# queso_dip_v5.net
KiCad netlist of a schematic drawn in EAGLE
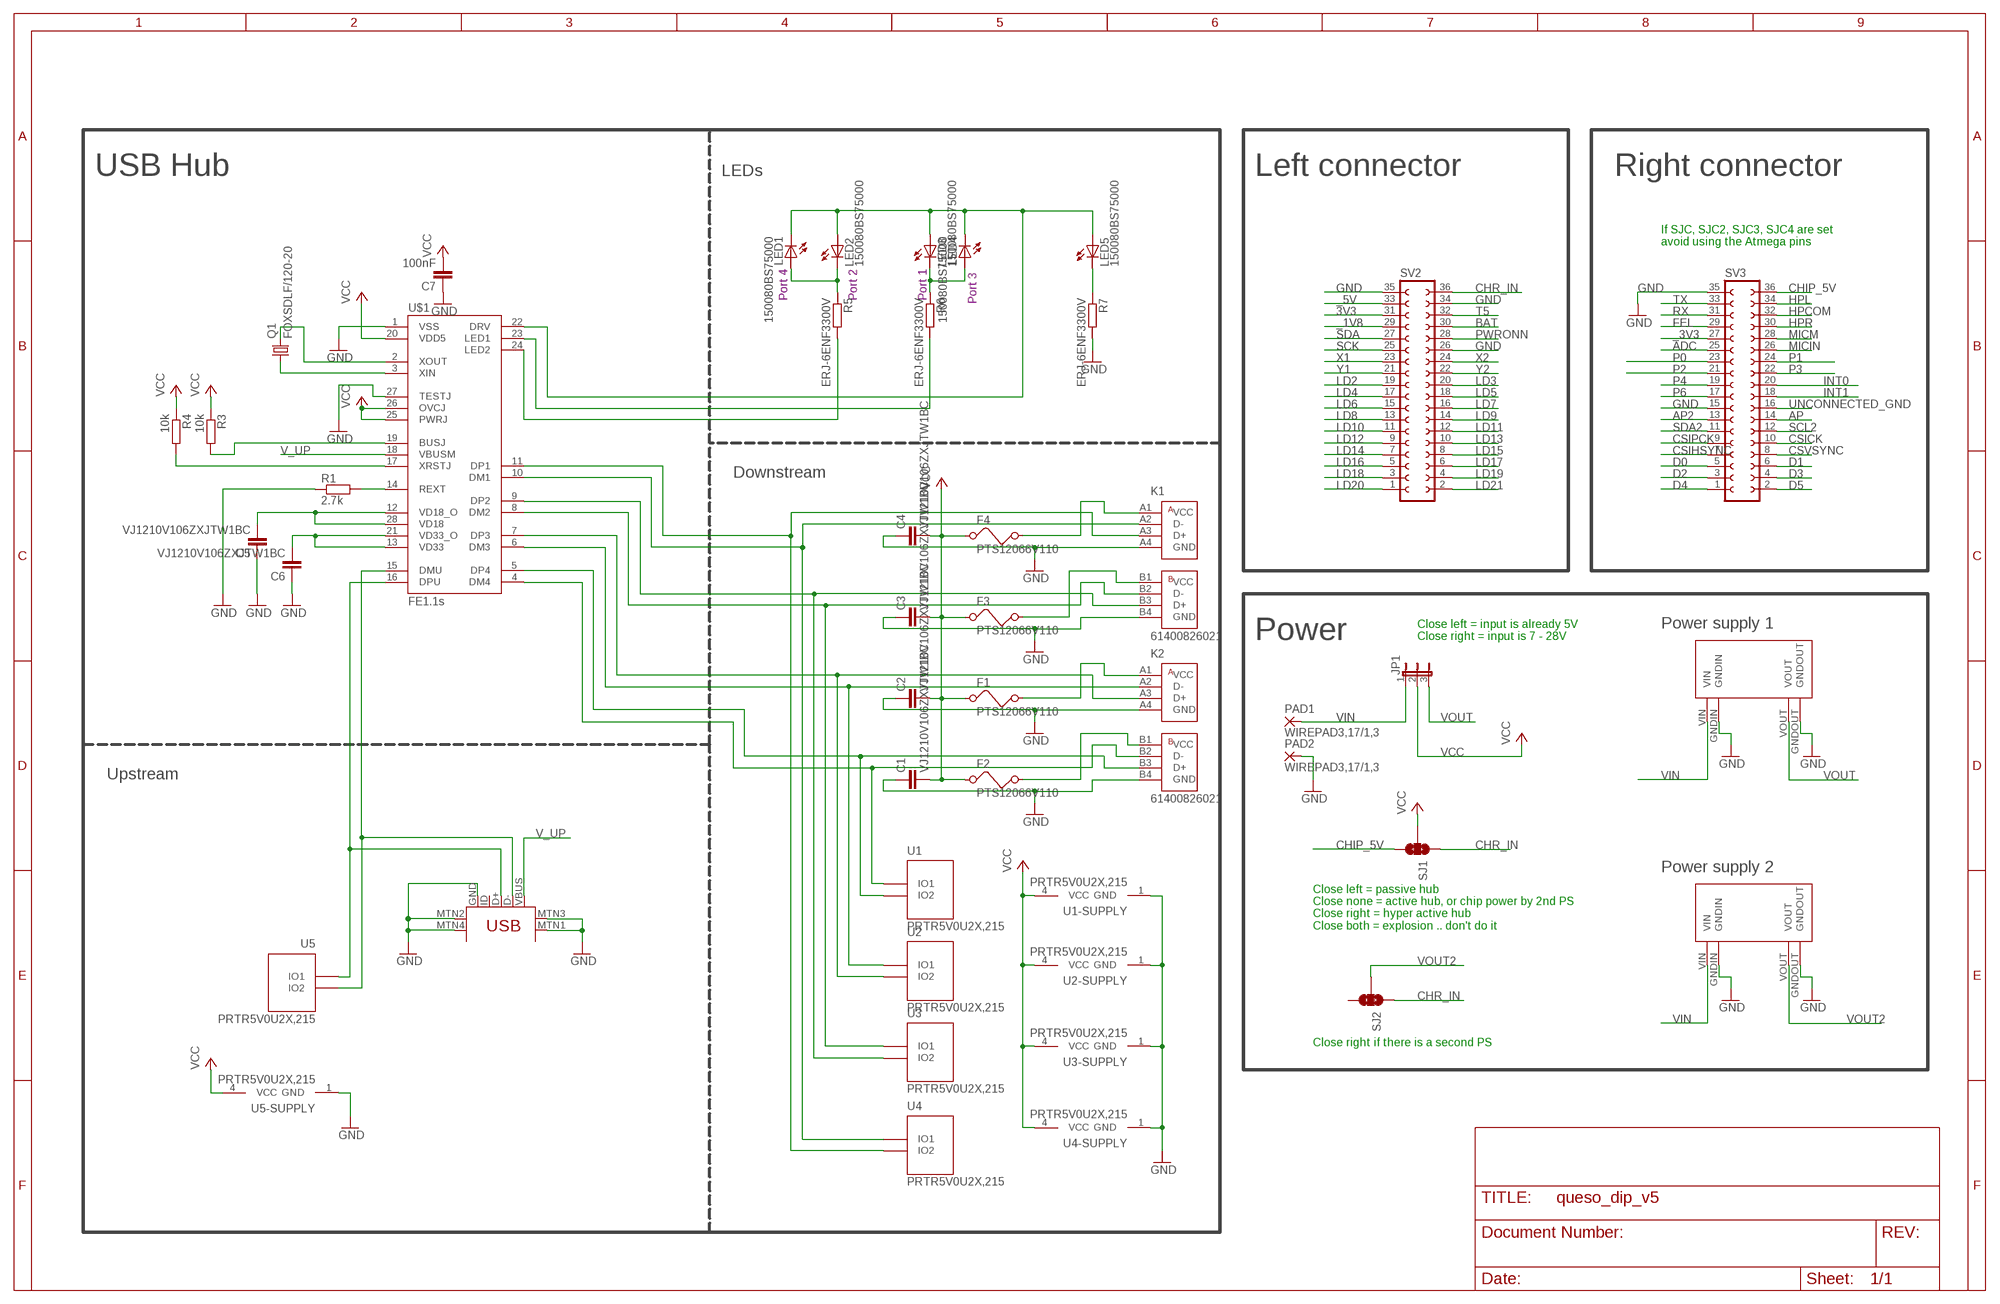
[diagram p0: schematic, sheet 1]

(export (version "E")
  (design (tool "Eeschema 10.0.6"))
  (components
    (comp (ref "C1")
      (value "VJ1210V106ZXJTW1BC")
      (footprint "eagle-import:C1210")
      (libsource (lib "eagle-import") (part "C-EUC1210"))
    )
    (comp (ref "C2")
      (value "VJ1210V106ZXJTW1BC")
      (footprint "eagle-import:C1210")
      (libsource (lib "eagle-import") (part "C-EUC1210"))
    )
    (comp (ref "C3")
      (value "VJ1210V106ZXJTW1BC")
      (footprint "eagle-import:C1210")
      (libsource (lib "eagle-import") (part "C-EUC1210"))
    )
    (comp (ref "C4")
      (value "VJ1210V106ZXJTW1BC")
      (footprint "eagle-import:C1210")
      (libsource (lib "eagle-import") (part "C-EUC1210"))
    )
    (comp (ref "C5")
      (value "VJ1210V106ZXJTW1BC")
      (footprint "eagle-import:C1210")
      (libsource (lib "eagle-import") (part "C-EUC1210"))
    )
    (comp (ref "C6")
      (value "VJ1210V106ZXJTW1BC")
      (footprint "eagle-import:C1210")
      (libsource (lib "eagle-import") (part "C-EUC1210"))
    )
    (comp (ref "C7")
      (value "100nF")
      (footprint "eagle-import:C0805")
      (libsource (lib "eagle-import") (part "C-EUC0805"))
    )
    (comp (ref "F1")
      (value "PTS12066V110")
      (footprint "eagle-import:1210")
      (libsource (lib "eagle-import") (part "FUSED"))
    )
    (comp (ref "F2")
      (value "PTS12066V110")
      (footprint "eagle-import:1210")
      (libsource (lib "eagle-import") (part "FUSED"))
    )
    (comp (ref "F3")
      (value "PTS12066V110")
      (footprint "eagle-import:1210")
      (libsource (lib "eagle-import") (part "FUSED"))
    )
    (comp (ref "F4")
      (value "PTS12066V110")
      (footprint "eagle-import:1210")
      (libsource (lib "eagle-import") (part "FUSED"))
    )
    (comp (ref "JP1")
      (value "JP2E")
      (footprint "eagle-import:JP2")
      (libsource (lib "eagle-import") (part "JP2E"))
    )
    (comp (ref "K1")
      (value "61400826021")
      (footprint "eagle-import:61400826021")
      (libsource (lib "eagle-import") (part "61400826021"))
    )
    (comp (ref "K2")
      (value "61400826021")
      (footprint "eagle-import:61400826021")
      (libsource (lib "eagle-import") (part "61400826021"))
    )
    (comp (ref "LED1")
      (value "150080BS75000")
      (footprint "eagle-import:CHIP-LED0805")
      (libsource (lib "eagle-import") (part "LEDCHIP-LED0805"))
    )
    (comp (ref "LED2")
      (value "150080BS75000")
      (footprint "eagle-import:CHIP-LED0805")
      (libsource (lib "eagle-import") (part "LEDCHIP-LED0805"))
    )
    (comp (ref "LED3")
      (value "150080BS75000")
      (footprint "eagle-import:CHIP-LED0805")
      (libsource (lib "eagle-import") (part "LEDCHIP-LED0805"))
    )
    (comp (ref "LED4")
      (value "150080BS75000")
      (footprint "eagle-import:CHIP-LED0805")
      (libsource (lib "eagle-import") (part "LEDCHIP-LED0805"))
    )
    (comp (ref "LED5")
      (value "150080BS75000")
      (footprint "eagle-import:CHIP-LED0805")
      (libsource (lib "eagle-import") (part "LEDCHIP-LED0805"))
    )
    (comp (ref "PAD1")
      (value "WIREPAD3,17/1,3")
      (footprint "eagle-import:3,17_1,3")
      (libsource (lib "eagle-import") (part "WIREPAD3,17/1,3"))
    )
    (comp (ref "PAD2")
      (value "WIREPAD3,17/1,3")
      (footprint "eagle-import:3,17_1,3")
      (libsource (lib "eagle-import") (part "WIREPAD3,17/1,3"))
    )
    (comp (ref "Q1")
      (value "FOXSDLF/120-20")
      (footprint "eagle-import:SM49")
      (libsource (lib "eagle-import") (part "CRYSTALSM49"))
    )
    (comp (ref "R1")
      (value "2.7k")
      (footprint "eagle-import:R0805")
      (libsource (lib "eagle-import") (part "R-EU_R0805"))
    )
    (comp (ref "R3")
      (value "10k")
      (footprint "eagle-import:R0805")
      (libsource (lib "eagle-import") (part "R-EU_R0805"))
    )
    (comp (ref "R4")
      (value "10k")
      (footprint "eagle-import:R0805")
      (libsource (lib "eagle-import") (part "R-EU_R0805"))
    )
    (comp (ref "R5")
      (value "ERJ-6ENF3300V")
      (footprint "eagle-import:R0805")
      (libsource (lib "eagle-import") (part "R-EU_R0805"))
    )
    (comp (ref "R6")
      (value "ERJ-6ENF3300V")
      (footprint "eagle-import:R0805")
      (libsource (lib "eagle-import") (part "R-EU_R0805"))
    )
    (comp (ref "R7")
      (value "ERJ-6ENF3300V")
      (footprint "eagle-import:R0805")
      (libsource (lib "eagle-import") (part "R-EU_R0805"))
    )
    (comp (ref "SJ1")
      (value "SOLDERJUMPER_2WAYT")
      (footprint "eagle-import:SJ_2")
      (libsource (lib "eagle-import") (part "SOLDERJUMPER_2WAYT"))
    )
    (comp (ref "SJ2")
      (value "SOLDERJUMPER_2WAYT")
      (footprint "eagle-import:SJ_2")
      (libsource (lib "eagle-import") (part "SOLDERJUMPER_2WAYT"))
    )
    (comp (ref "SV2")
      (value "FE18-2")
      (footprint "eagle-import:FE18-2")
      (libsource (lib "eagle-import") (part "FE18-2"))
    )
    (comp (ref "SV3")
      (value "FE18-2")
      (footprint "eagle-import:FE18-2")
      (libsource (lib "eagle-import") (part "FE18-2"))
    )
    (comp (ref "U$1")
      (value "FE1.1S")
      (footprint "eagle-import:FE1.1S_SSOP-28")
      (libsource (lib "eagle-import") (part "FE1.1S"))
    )
    (comp (ref "U$3")
      (value "MP1584EN")
      (footprint "eagle-import:MP1584EN")
      (libsource (lib "eagle-import") (part "MP1584EN"))
    )
    (comp (ref "U$8")
      (value "10118194-0001LF")
      (footprint "eagle-import:USB-MINIB")
      (libsource (lib "eagle-import") (part "USB-MINIB-5PIN"))
    )
    (comp (ref "U$9")
      (value "MP1584EN")
      (footprint "eagle-import:MP1584EN")
      (libsource (lib "eagle-import") (part "MP1584EN"))
    )
    (comp (ref "U1")
      (value "PRTR5V0U2X,215")
      (footprint "eagle-import:SOT-143B")
      (fields (field (name "MANUFACTURER") "NXP Semiconductors"))
      (libsource (lib "eagle-import") (part "PRTR5V0U2X?"))
    )
    (comp (ref "U2")
      (value "PRTR5V0U2X,215")
      (footprint "eagle-import:SOT-143B")
      (fields (field (name "MANUFACTURER") "NXP Semiconductors"))
      (libsource (lib "eagle-import") (part "PRTR5V0U2X?"))
    )
    (comp (ref "U3")
      (value "PRTR5V0U2X,215")
      (footprint "eagle-import:SOT-143B")
      (fields (field (name "MANUFACTURER") "NXP Semiconductors"))
      (libsource (lib "eagle-import") (part "PRTR5V0U2X?"))
    )
    (comp (ref "U4")
      (value "PRTR5V0U2X,215")
      (footprint "eagle-import:SOT-143B")
      (fields (field (name "MANUFACTURER") "NXP Semiconductors"))
      (libsource (lib "eagle-import") (part "PRTR5V0U2X?"))
    )
    (comp (ref "U5")
      (value "PRTR5V0U2X,215")
      (footprint "eagle-import:SOT-143B")
      (fields (field (name "MANUFACTURER") "NXP Semiconductors"))
      (libsource (lib "eagle-import") (part "PRTR5V0U2X?"))
    )
  )
  (nets
    (net (code "1") (name "/3V3") (class "Default")
      (node (ref "SV2") (pin "31") (pinfunction "31_31") (pintype "passive"))
    )
    (net (code "2") (name "/ADC") (class "Default")
      (node (ref "SV3") (pin "25") (pinfunction "25_25") (pintype "passive"))
    )
    (net (code "3") (name "/AP") (class "Default")
      (node (ref "SV3") (pin "14") (pinfunction "14_14") (pintype "passive"))
    )
    (net (code "4") (name "/AP2") (class "Default")
      (node (ref "SV3") (pin "13") (pinfunction "13_13") (pintype "passive"))
    )
    (net (code "5") (name "/BAT") (class "Default")
      (node (ref "SV2") (pin "30") (pinfunction "30_30") (pintype "passive"))
    )
    (net (code "6") (name "/CHIP_5V") (class "Default")
      (node (ref "SJ1") (pin "3") (pinfunction "3_3") (pintype "passive"))
      (node (ref "SV3") (pin "36") (pinfunction "36_36") (pintype "passive"))
    )
    (net (code "7") (name "/CHR_IN") (class "Default")
      (node (ref "SJ1") (pin "1") (pinfunction "1_1") (pintype "passive"))
      (node (ref "SJ2") (pin "1") (pinfunction "1_1") (pintype "passive"))
      (node (ref "SV2") (pin "36") (pinfunction "36_36") (pintype "passive"))
    )
    (net (code "8") (name "/CSICK") (class "Default")
      (node (ref "SV3") (pin "10") (pinfunction "10_10") (pintype "passive"))
    )
    (net (code "9") (name "/CSIHSYNC") (class "Default")
      (node (ref "SV3") (pin "7") (pinfunction "7_7") (pintype "passive"))
    )
    (net (code "10") (name "/CSIPCK") (class "Default")
      (node (ref "SV3") (pin "9") (pinfunction "9_9") (pintype "passive"))
    )
    (net (code "11") (name "/CSVSYNC") (class "Default")
      (node (ref "SV3") (pin "8") (pinfunction "8_8") (pintype "passive"))
    )
    (net (code "12") (name "/D0") (class "Default")
      (node (ref "SV3") (pin "5") (pinfunction "5_5") (pintype "passive"))
    )
    (net (code "13") (name "/D1") (class "Default")
      (node (ref "SV3") (pin "6") (pinfunction "6_6") (pintype "passive"))
    )
    (net (code "14") (name "/D2") (class "Default")
      (node (ref "SV3") (pin "3") (pinfunction "3_3") (pintype "passive"))
    )
    (net (code "15") (name "/D3") (class "Default")
      (node (ref "SV3") (pin "4") (pinfunction "4_4") (pintype "passive"))
    )
    (net (code "16") (name "/D4") (class "Default")
      (node (ref "SV3") (pin "1") (pinfunction "1_1") (pintype "passive"))
    )
    (net (code "17") (name "/D5") (class "Default")
      (node (ref "SV3") (pin "2") (pinfunction "2_2") (pintype "passive"))
    )
    (net (code "18") (name "/FEL") (class "Default")
      (node (ref "SV3") (pin "29") (pinfunction "29_29") (pintype "passive"))
    )
    (net (code "19") (name "/HPCOM") (class "Default")
      (node (ref "SV3") (pin "32") (pinfunction "32_32") (pintype "passive"))
    )
    (net (code "20") (name "/HPL") (class "Default")
      (node (ref "SV3") (pin "34") (pinfunction "34_34") (pintype "passive"))
    )
    (net (code "21") (name "/HPR") (class "Default")
      (node (ref "SV3") (pin "30") (pinfunction "30_30") (pintype "passive"))
    )
    (net (code "22") (name "/INT0") (class "Default")
      (node (ref "SV3") (pin "20") (pinfunction "20_20") (pintype "passive"))
    )
    (net (code "23") (name "/INT1") (class "Default")
      (node (ref "SV3") (pin "18") (pinfunction "18_18") (pintype "passive"))
    )
    (net (code "24") (name "/LD2") (class "Default")
      (node (ref "SV2") (pin "19") (pinfunction "19_19") (pintype "passive"))
    )
    (net (code "25") (name "/LD3") (class "Default")
      (node (ref "SV2") (pin "20") (pinfunction "20_20") (pintype "passive"))
    )
    (net (code "26") (name "/LD4") (class "Default")
      (node (ref "SV2") (pin "17") (pinfunction "17_17") (pintype "passive"))
    )
    (net (code "27") (name "/LD5") (class "Default")
      (node (ref "SV2") (pin "18") (pinfunction "18_18") (pintype "passive"))
    )
    (net (code "28") (name "/LD6") (class "Default")
      (node (ref "SV2") (pin "15") (pinfunction "15_15") (pintype "passive"))
    )
    (net (code "29") (name "/LD7") (class "Default")
      (node (ref "SV2") (pin "16") (pinfunction "16_16") (pintype "passive"))
    )
    (net (code "30") (name "/LD8") (class "Default")
      (node (ref "SV2") (pin "13") (pinfunction "13_13") (pintype "passive"))
    )
    (net (code "31") (name "/LD9") (class "Default")
      (node (ref "SV2") (pin "14") (pinfunction "14_14") (pintype "passive"))
    )
    (net (code "32") (name "/LD10") (class "Default")
      (node (ref "SV2") (pin "11") (pinfunction "11_11") (pintype "passive"))
    )
    (net (code "33") (name "/LD11") (class "Default")
      (node (ref "SV2") (pin "12") (pinfunction "12_12") (pintype "passive"))
    )
    (net (code "34") (name "/LD12") (class "Default")
      (node (ref "SV2") (pin "9") (pinfunction "9_9") (pintype "passive"))
    )
    (net (code "35") (name "/LD13") (class "Default")
      (node (ref "SV2") (pin "10") (pinfunction "10_10") (pintype "passive"))
    )
    (net (code "36") (name "/LD14") (class "Default")
      (node (ref "SV2") (pin "7") (pinfunction "7_7") (pintype "passive"))
    )
    (net (code "37") (name "/LD15") (class "Default")
      (node (ref "SV2") (pin "8") (pinfunction "8_8") (pintype "passive"))
    )
    (net (code "38") (name "/LD16") (class "Default")
      (node (ref "SV2") (pin "5") (pinfunction "5_5") (pintype "passive"))
    )
    (net (code "39") (name "/LD17") (class "Default")
      (node (ref "SV2") (pin "6") (pinfunction "6_6") (pintype "passive"))
    )
    (net (code "40") (name "/LD18") (class "Default")
      (node (ref "SV2") (pin "3") (pinfunction "3_3") (pintype "passive"))
    )
    (net (code "41") (name "/LD19") (class "Default")
      (node (ref "SV2") (pin "4") (pinfunction "4_4") (pintype "passive"))
    )
    (net (code "42") (name "/LD20") (class "Default")
      (node (ref "SV2") (pin "1") (pinfunction "1_1") (pintype "passive"))
    )
    (net (code "43") (name "/LD21") (class "Default")
      (node (ref "SV2") (pin "2") (pinfunction "2_2") (pintype "passive"))
    )
    (net (code "44") (name "/MICIN") (class "Default")
      (node (ref "SV3") (pin "26") (pinfunction "26_26") (pintype "passive"))
    )
    (net (code "45") (name "/MICM") (class "Default")
      (node (ref "SV3") (pin "28") (pinfunction "28_28") (pintype "passive"))
    )
    (net (code "46") (name "/P0") (class "Default")
      (node (ref "SV3") (pin "23") (pinfunction "23_23") (pintype "passive"))
    )
    (net (code "47") (name "/P1") (class "Default")
      (node (ref "SV3") (pin "24") (pinfunction "24_24") (pintype "passive"))
    )
    (net (code "48") (name "/P2") (class "Default")
      (node (ref "SV3") (pin "21") (pinfunction "21_21") (pintype "passive"))
    )
    (net (code "49") (name "/P3") (class "Default")
      (node (ref "SV3") (pin "22") (pinfunction "22_22") (pintype "passive"))
    )
    (net (code "50") (name "/P4") (class "Default")
      (node (ref "SV3") (pin "19") (pinfunction "19_19") (pintype "passive"))
    )
    (net (code "51") (name "/P6") (class "Default")
      (node (ref "SV3") (pin "17") (pinfunction "17_17") (pintype "passive"))
    )
    (net (code "52") (name "/PWRONN") (class "Default")
      (node (ref "SV2") (pin "28") (pinfunction "28_28") (pintype "passive"))
    )
    (net (code "53") (name "/RX") (class "Default")
      (node (ref "SV3") (pin "31") (pinfunction "31_31") (pintype "passive"))
    )
    (net (code "54") (name "/SCK") (class "Default")
      (node (ref "SV2") (pin "25") (pinfunction "25_25") (pintype "passive"))
    )
    (net (code "55") (name "/SCL2") (class "Default")
      (node (ref "SV3") (pin "12") (pinfunction "12_12") (pintype "passive"))
    )
    (net (code "56") (name "/SDA") (class "Default")
      (node (ref "SV2") (pin "27") (pinfunction "27_27") (pintype "passive"))
    )
    (net (code "57") (name "/SDA2") (class "Default")
      (node (ref "SV3") (pin "11") (pinfunction "11_11") (pintype "passive"))
    )
    (net (code "58") (name "/T5") (class "Default")
      (node (ref "SV2") (pin "32") (pinfunction "32_32") (pintype "passive"))
    )
    (net (code "59") (name "/TX") (class "Default")
      (node (ref "SV3") (pin "33") (pinfunction "33_33") (pintype "passive"))
    )
    (net (code "60") (name "/UNCONNECTED_GND") (class "Default")
      (node (ref "SV3") (pin "16") (pinfunction "16_16") (pintype "passive"))
    )
    (net (code "61") (name "/VIN") (class "Default")
      (node (ref "JP1") (pin "1") (pinfunction "1_1") (pintype "passive"))
      (node (ref "PAD1") (pin "1") (pinfunction "P_1") (pintype "passive"))
      (node (ref "U$3") (pin "VIN") (pinfunction "VIN_VIN") (pintype "power_in"))
      (node (ref "U$9") (pin "VIN") (pinfunction "VIN_VIN") (pintype "power_in"))
    )
    (net (code "62") (name "/VOUT") (class "Default")
      (node (ref "JP1") (pin "3") (pinfunction "3_3") (pintype "passive"))
      (node (ref "U$9") (pin "VOUT") (pinfunction "VOUT_VOUT") (pintype "power_in"))
    )
    (net (code "63") (name "/VOUT2") (class "Default")
      (node (ref "SJ2") (pin "2") (pinfunction "2_2") (pintype "passive"))
      (node (ref "U$3") (pin "VOUT") (pinfunction "VOUT_VOUT") (pintype "power_in"))
    )
    (net (code "64") (name "/V_UP") (class "Default")
      (node (ref "U$1") (pin "18") (pinfunction "VBUSM_18") (pintype "bidirectional"))
      (node (ref "U$8") (pin "VBUS") (pinfunction "VBUS_VBUS") (pintype "bidirectional"))
    )
    (net (code "65") (name "/X1") (class "Default")
      (node (ref "SV2") (pin "23") (pinfunction "23_23") (pintype "passive"))
    )
    (net (code "66") (name "/X2") (class "Default")
      (node (ref "SV2") (pin "24") (pinfunction "24_24") (pintype "passive"))
    )
    (net (code "67") (name "/Y1") (class "Default")
      (node (ref "SV2") (pin "21") (pinfunction "21_21") (pintype "passive"))
    )
    (net (code "68") (name "/Y2") (class "Default")
      (node (ref "SV2") (pin "22") (pinfunction "22_22") (pintype "passive"))
    )
    (net (code "69") (name "/_1V8") (class "Default")
      (node (ref "SV2") (pin "29") (pinfunction "29_29") (pintype "passive"))
    )
    (net (code "70") (name "/_3V3") (class "Default")
      (node (ref "SV3") (pin "27") (pinfunction "27_27") (pintype "passive"))
    )
    (net (code "71") (name "/_5V") (class "Default")
      (node (ref "SV2") (pin "33") (pinfunction "33_33") (pintype "passive"))
    )
    (net (code "72") (name "GND") (class "Default")
      (node (ref "C1") (pin "1") (pinfunction "1_1") (pintype "passive"))
      (node (ref "C2") (pin "1") (pinfunction "1_1") (pintype "passive"))
      (node (ref "C3") (pin "1") (pinfunction "1_1") (pintype "passive"))
      (node (ref "C4") (pin "1") (pinfunction "1_1") (pintype "passive"))
      (node (ref "C5") (pin "1") (pinfunction "1_1") (pintype "passive"))
      (node (ref "C6") (pin "1") (pinfunction "1_1") (pintype "passive"))
      (node (ref "C7") (pin "1") (pinfunction "1_1") (pintype "passive"))
      (node (ref "K1") (pin "A4") (pinfunction "GND_A4") (pintype "bidirectional"))
      (node (ref "K1") (pin "B4") (pinfunction "GND_B4") (pintype "bidirectional"))
      (node (ref "K2") (pin "A4") (pinfunction "GND_A4") (pintype "bidirectional"))
      (node (ref "K2") (pin "B4") (pinfunction "GND_B4") (pintype "bidirectional"))
      (node (ref "PAD2") (pin "1") (pinfunction "P_1") (pintype "passive"))
      (node (ref "R1") (pin "1") (pinfunction "1_1") (pintype "passive"))
      (node (ref "R7") (pin "2") (pinfunction "2_2") (pintype "passive"))
      (node (ref "SV2") (pin "26") (pinfunction "26_26") (pintype "passive"))
      (node (ref "SV2") (pin "34") (pinfunction "34_34") (pintype "passive"))
      (node (ref "SV2") (pin "35") (pinfunction "35_35") (pintype "passive"))
      (node (ref "SV3") (pin "15") (pinfunction "15_15") (pintype "passive"))
      (node (ref "SV3") (pin "35") (pinfunction "35_35") (pintype "passive"))
      (node (ref "U$1") (pin "1") (pinfunction "VSS_1") (pintype "bidirectional"))
      (node (ref "U$1") (pin "27") (pinfunction "TESTJ_27") (pintype "bidirectional"))
      (node (ref "U$3") (pin "GNDIN") (pinfunction "GNDIN_GNDIN") (pintype "power_in"))
      (node (ref "U$3") (pin "GNDOUT") (pinfunction "GNDOUT_GNDOUT") (pintype "power_in"))
      (node (ref "U$8") (pin "GND") (pinfunction "GND_GND") (pintype "bidirectional"))
      (node (ref "U$8") (pin "MTN1") (pinfunction "MTN2_MTN1") (pintype "bidirectional"))
      (node (ref "U$8") (pin "MTN2") (pinfunction "MTN3_MTN2") (pintype "bidirectional"))
      (node (ref "U$8") (pin "MTN3") (pinfunction "MTN1_MTN3") (pintype "bidirectional"))
      (node (ref "U$8") (pin "MTN4") (pinfunction "MTN4_MTN4") (pintype "bidirectional"))
      (node (ref "U$9") (pin "GNDIN") (pinfunction "GNDIN_GNDIN") (pintype "power_in"))
      (node (ref "U$9") (pin "GNDOUT") (pinfunction "GNDOUT_GNDOUT") (pintype "power_in"))
      (node (ref "U1") (pin "1") (pinfunction "GND_1") (pintype "bidirectional"))
      (node (ref "U2") (pin "1") (pinfunction "GND_1") (pintype "bidirectional"))
      (node (ref "U3") (pin "1") (pinfunction "GND_1") (pintype "bidirectional"))
      (node (ref "U4") (pin "1") (pinfunction "GND_1") (pintype "bidirectional"))
      (node (ref "U5") (pin "1") (pinfunction "GND_1") (pintype "bidirectional"))
    )
    (net (code "73") (name "Net-(F1-Pad2)") (class "Default")
      (node (ref "F1") (pin "2") (pinfunction "2_2") (pintype "passive"))
      (node (ref "K2") (pin "A1") (pinfunction "VCC_A1") (pintype "bidirectional"))
    )
    (net (code "74") (name "Net-(F2-Pad2)") (class "Default")
      (node (ref "F2") (pin "2") (pinfunction "2_2") (pintype "passive"))
      (node (ref "K2") (pin "B1") (pinfunction "VCC_B1") (pintype "bidirectional"))
    )
    (net (code "75") (name "Net-(F3-Pad2)") (class "Default")
      (node (ref "F3") (pin "2") (pinfunction "2_2") (pintype "passive"))
      (node (ref "K1") (pin "B1") (pinfunction "VCC_B1") (pintype "bidirectional"))
    )
    (net (code "76") (name "Net-(F4-Pad2)") (class "Default")
      (node (ref "F4") (pin "2") (pinfunction "2_2") (pintype "passive"))
      (node (ref "K1") (pin "A1") (pinfunction "VCC_A1") (pintype "bidirectional"))
    )
    (net (code "77") (name "Net-(LED1-PadA)") (class "Default")
      (node (ref "LED1") (pin "A") (pinfunction "A_A") (pintype "passive"))
      (node (ref "LED2") (pin "C") (pinfunction "C_C") (pintype "passive"))
      (node (ref "R5") (pin "1") (pinfunction "1_1") (pintype "passive"))
    )
    (net (code "78") (name "Net-(LED3-PadC)") (class "Default")
      (node (ref "LED3") (pin "C") (pinfunction "C_C") (pintype "passive"))
      (node (ref "LED4") (pin "A") (pinfunction "A_A") (pintype "passive"))
      (node (ref "R6") (pin "1") (pinfunction "1_1") (pintype "passive"))
    )
    (net (code "79") (name "Net-(LED5-PadC)") (class "Default")
      (node (ref "LED5") (pin "C") (pinfunction "C_C") (pintype "passive"))
      (node (ref "R7") (pin "1") (pinfunction "1_1") (pintype "passive"))
    )
    (net (code "80") (name "Net-(U$1-BUSJ)") (class "Default")
      (node (ref "R3") (pin "2") (pinfunction "2_2") (pintype "passive"))
      (node (ref "U$1") (pin "19") (pinfunction "BUSJ_19") (pintype "bidirectional"))
    )
    (net (code "81") (name "Net-(U$1-DM1)") (class "Default")
      (node (ref "K1") (pin "A2") (pinfunction "D-_A2") (pintype "bidirectional"))
      (node (ref "U$1") (pin "10") (pinfunction "DM1_10") (pintype "bidirectional"))
      (node (ref "U4") (pin "2") (pinfunction "IO1_2") (pintype "bidirectional"))
    )
    (net (code "82") (name "Net-(U$1-DM2)") (class "Default")
      (node (ref "K1") (pin "B2") (pinfunction "D-_B2") (pintype "bidirectional"))
      (node (ref "U$1") (pin "8") (pinfunction "DM2_8") (pintype "bidirectional"))
      (node (ref "U3") (pin "2") (pinfunction "IO1_2") (pintype "bidirectional"))
    )
    (net (code "83") (name "Net-(U$1-DM3)") (class "Default")
      (node (ref "K2") (pin "A2") (pinfunction "D-_A2") (pintype "bidirectional"))
      (node (ref "U$1") (pin "6") (pinfunction "DM3_6") (pintype "bidirectional"))
      (node (ref "U2") (pin "2") (pinfunction "IO1_2") (pintype "bidirectional"))
    )
    (net (code "84") (name "Net-(U$1-DM4)") (class "Default")
      (node (ref "K2") (pin "B2") (pinfunction "D-_B2") (pintype "bidirectional"))
      (node (ref "U$1") (pin "4") (pinfunction "DM4_4") (pintype "bidirectional"))
      (node (ref "U1") (pin "2") (pinfunction "IO1_2") (pintype "bidirectional"))
    )
    (net (code "85") (name "Net-(U$1-DMU)") (class "Default")
      (node (ref "U$1") (pin "15") (pinfunction "DMU_15") (pintype "bidirectional"))
      (node (ref "U$8") (pin "D-") (pinfunction "D-_D-") (pintype "bidirectional"))
      (node (ref "U5") (pin "3") (pinfunction "IO2_3") (pintype "bidirectional"))
    )
    (net (code "86") (name "Net-(U$1-DP1)") (class "Default")
      (node (ref "K1") (pin "A3") (pinfunction "D+_A3") (pintype "bidirectional"))
      (node (ref "U$1") (pin "11") (pinfunction "DP1_11") (pintype "bidirectional"))
      (node (ref "U4") (pin "3") (pinfunction "IO2_3") (pintype "bidirectional"))
    )
    (net (code "87") (name "Net-(U$1-DP2)") (class "Default")
      (node (ref "K1") (pin "B3") (pinfunction "D+_B3") (pintype "bidirectional"))
      (node (ref "U$1") (pin "9") (pinfunction "DP2_9") (pintype "bidirectional"))
      (node (ref "U3") (pin "3") (pinfunction "IO2_3") (pintype "bidirectional"))
    )
    (net (code "88") (name "Net-(U$1-DP3)") (class "Default")
      (node (ref "K2") (pin "A3") (pinfunction "D+_A3") (pintype "bidirectional"))
      (node (ref "U$1") (pin "7") (pinfunction "DP3_7") (pintype "bidirectional"))
      (node (ref "U2") (pin "3") (pinfunction "IO2_3") (pintype "bidirectional"))
    )
    (net (code "89") (name "Net-(U$1-DP4)") (class "Default")
      (node (ref "K2") (pin "B3") (pinfunction "D+_B3") (pintype "bidirectional"))
      (node (ref "U$1") (pin "5") (pinfunction "DP4_5") (pintype "bidirectional"))
      (node (ref "U1") (pin "3") (pinfunction "IO2_3") (pintype "bidirectional"))
    )
    (net (code "90") (name "Net-(U$1-DPU)") (class "Default")
      (node (ref "U$1") (pin "16") (pinfunction "DPU_16") (pintype "bidirectional"))
      (node (ref "U$8") (pin "D+") (pinfunction "D+_D+") (pintype "bidirectional"))
      (node (ref "U5") (pin "2") (pinfunction "IO1_2") (pintype "bidirectional"))
    )
    (net (code "91") (name "Net-(U$1-DRV)") (class "Default")
      (node (ref "LED1") (pin "C") (pinfunction "C_C") (pintype "passive"))
      (node (ref "LED2") (pin "A") (pinfunction "A_A") (pintype "passive"))
      (node (ref "LED3") (pin "A") (pinfunction "A_A") (pintype "passive"))
      (node (ref "LED4") (pin "C") (pinfunction "C_C") (pintype "passive"))
      (node (ref "LED5") (pin "A") (pinfunction "A_A") (pintype "passive"))
      (node (ref "U$1") (pin "22") (pinfunction "DRV_22") (pintype "bidirectional"))
    )
    (net (code "92") (name "Net-(U$1-LED1)") (class "Default")
      (node (ref "R6") (pin "2") (pinfunction "2_2") (pintype "passive"))
      (node (ref "U$1") (pin "23") (pinfunction "LED1_23") (pintype "bidirectional"))
    )
    (net (code "93") (name "Net-(U$1-LED2)") (class "Default")
      (node (ref "R5") (pin "2") (pinfunction "2_2") (pintype "passive"))
      (node (ref "U$1") (pin "24") (pinfunction "LED2_24") (pintype "bidirectional"))
    )
    (net (code "94") (name "Net-(U$1-REXT)") (class "Default")
      (node (ref "R1") (pin "2") (pinfunction "2_2") (pintype "passive"))
      (node (ref "U$1") (pin "14") (pinfunction "REXT_14") (pintype "bidirectional"))
    )
    (net (code "95") (name "Net-(U$1-VD18)") (class "Default")
      (node (ref "C5") (pin "2") (pinfunction "2_2") (pintype "passive"))
      (node (ref "U$1") (pin "12") (pinfunction "VD18_O_12") (pintype "bidirectional"))
      (node (ref "U$1") (pin "28") (pinfunction "VD18_28") (pintype "bidirectional"))
    )
    (net (code "96") (name "Net-(U$1-VD33)") (class "Default")
      (node (ref "C6") (pin "2") (pinfunction "2_2") (pintype "passive"))
      (node (ref "U$1") (pin "13") (pinfunction "VD33_13") (pintype "bidirectional"))
      (node (ref "U$1") (pin "21") (pinfunction "VD33_O_21") (pintype "bidirectional"))
    )
    (net (code "97") (name "Net-(U$1-XIN)") (class "Default")
      (node (ref "Q1") (pin "1") (pinfunction "1_1") (pintype "passive"))
      (node (ref "U$1") (pin "3") (pinfunction "XIN_3") (pintype "bidirectional"))
    )
    (net (code "98") (name "Net-(U$1-XOUT)") (class "Default")
      (node (ref "Q1") (pin "2") (pinfunction "2_2") (pintype "passive"))
      (node (ref "U$1") (pin "2") (pinfunction "XOUT_2") (pintype "bidirectional"))
    )
    (net (code "99") (name "Net-(U$1-XRSTJ)") (class "Default")
      (node (ref "R4") (pin "2") (pinfunction "2_2") (pintype "passive"))
      (node (ref "U$1") (pin "17") (pinfunction "XRSTJ_17") (pintype "bidirectional"))
    )
    (net (code "100") (name "VCC") (class "Default")
      (node (ref "C1") (pin "2") (pinfunction "2_2") (pintype "passive"))
      (node (ref "C2") (pin "2") (pinfunction "2_2") (pintype "passive"))
      (node (ref "C3") (pin "2") (pinfunction "2_2") (pintype "passive"))
      (node (ref "C4") (pin "2") (pinfunction "2_2") (pintype "passive"))
      (node (ref "C7") (pin "2") (pinfunction "2_2") (pintype "passive"))
      (node (ref "F1") (pin "1") (pinfunction "1_1") (pintype "passive"))
      (node (ref "F2") (pin "1") (pinfunction "1_1") (pintype "passive"))
      (node (ref "F3") (pin "1") (pinfunction "1_1") (pintype "passive"))
      (node (ref "F4") (pin "1") (pinfunction "1_1") (pintype "passive"))
      (node (ref "JP1") (pin "2") (pinfunction "2_2") (pintype "passive"))
      (node (ref "R3") (pin "1") (pinfunction "1_1") (pintype "passive"))
      (node (ref "R4") (pin "1") (pinfunction "1_1") (pintype "passive"))
      (node (ref "SJ1") (pin "2") (pinfunction "2_2") (pintype "passive"))
      (node (ref "U$1") (pin "20") (pinfunction "VDD5_20") (pintype "bidirectional"))
      (node (ref "U$1") (pin "25") (pinfunction "PWRJ_25") (pintype "bidirectional"))
      (node (ref "U$1") (pin "26") (pinfunction "OVCJ_26") (pintype "bidirectional"))
      (node (ref "U1") (pin "4") (pinfunction "VCC_4") (pintype "bidirectional"))
      (node (ref "U2") (pin "4") (pinfunction "VCC_4") (pintype "bidirectional"))
      (node (ref "U3") (pin "4") (pinfunction "VCC_4") (pintype "bidirectional"))
      (node (ref "U4") (pin "4") (pinfunction "VCC_4") (pintype "bidirectional"))
      (node (ref "U5") (pin "4") (pinfunction "VCC_4") (pintype "bidirectional"))
    )
    (net (code "101") (name "unconnected-(SJ2-Pad3)") (class "Default")
      (node (ref "SJ2") (pin "3") (pinfunction "3_3") (pintype "passive"))
    )
    (net (code "102") (name "unconnected-(U$8-PadID)") (class "Default")
      (node (ref "U$8") (pin "ID") (pinfunction "ID_ID") (pintype "bidirectional"))
    )
  )
)
